# 08-USB_OTG.net
KiCad netlist of a schematic drawn in Altium Designer
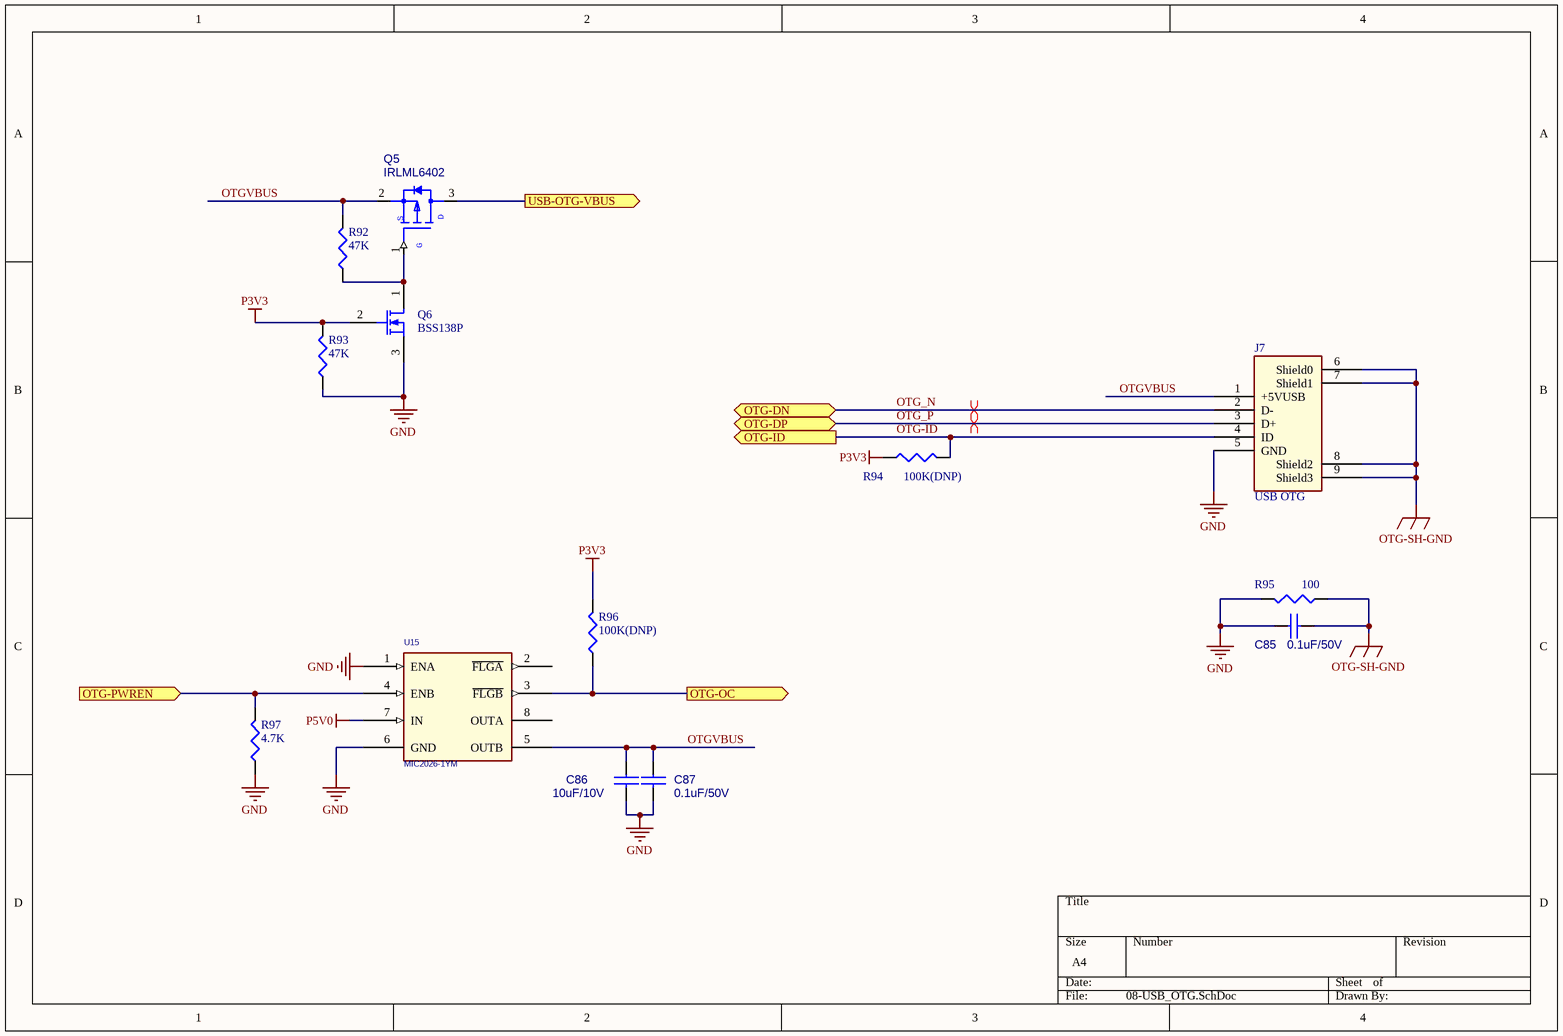
[diagram p0: 08-USB_OTG.SchDoc]

(export (version "E")
  (design (tool "Eeschema 10.0.6"))
  (components
    (comp (ref "C85") (value "0.1uF/50V") (libsource (lib "*") (part "CAP_Dup1")))
    (comp (ref "C86") (value "10uF/10V") (libsource (lib "*") (part "CAP_Dup1")))
    (comp (ref "C87") (value "0.1uF/50V") (libsource (lib "*") (part "CAP_Dup1")))
    (comp (ref "J7")
      (value "USB OTG")
      (footprint "MINIUSB-TYPEAB")
      (fields (field (name "PART NUMBER") "SP063100800"))
      (libsource (lib "*") (part "FOX_UH51543-JS7"))
    )
    (comp (ref "Q5")
      (value "IRLML6402")
      (footprint "MOSFET")
      (fields (field (name "PART NUMBER") "SB934010010"))
      (libsource (lib "*") (part "AO3401L_SOT23-3_0"))
    )
    (comp (ref "Q6")
      (value "BSS138P")
      (footprint "NPN")
      (description "N-Channel MOSFET")
      (fields (field (name "PUBLISHER") "Altium Limited"))
      (libsource (lib "Miscellaneous Devices") (part "MOSFET-N"))
    )
    (comp (ref "R92") (value "47K") (footprint "0402") (libsource (lib "*") (part "CR16-1003FM")))
    (comp (ref "R93") (value "47K") (footprint "0402") (libsource (lib "*") (part "CR16-1003FM")))
    (comp (ref "R94") (value "100K(DNP)") (footprint "0402") (libsource (lib "*") (part "CR16-1003FM")))
    (comp (ref "R95") (value "100") (footprint "0402") (libsource (lib "*") (part "CR16-1003FM")))
    (comp (ref "R96") (value "100K(DNP)") (footprint "0402") (libsource (lib "*") (part "CR16-1003FM")))
    (comp (ref "R97") (value "4.7K") (footprint "0402") (libsource (lib "*") (part "CR16-1003FM")))
    (comp (ref "U15")
      (value "MIC2026-1YM")
      (footprint "SO8")
      (description "IC LIN SW PWR ACTIVE HIGH DUAL 2.7V-5.5V 0.5A SOIC8")
      (libsource (lib "*") (part "MIC2526_8P"))
    )
  )
  (nets
    (net (code "1") (name "/OTG-ID") (class "Default")
      (node (ref "J7") (pin "4") (pinfunction "ID_4") (pintype "passive"))
      (node (ref "R94") (pin "2") (pinfunction "2_2") (pintype "passive"))
    )
    (net (code "2") (name "/OTG-OC") (class "Default")
      (node (ref "R96") (pin "1") (pinfunction "1_1") (pintype "passive"))
      (node (ref "U15") (pin "3") (pinfunction "~{FLGB}_3") (pintype "output"))
    )
    (net (code "3") (name "/OTG-PWREN") (class "Default")
      (node (ref "R97") (pin "2") (pinfunction "2_2") (pintype "passive"))
      (node (ref "U15") (pin "4") (pinfunction "ENB_4") (pintype "input"))
    )
    (net (code "4") (name "/OTGVBUS") (class "Default")
      (node (ref "C86") (pin "1") (pinfunction "1_1") (pintype "passive"))
      (node (ref "C87") (pin "1") (pinfunction "1_1") (pintype "passive"))
      (node (ref "J7") (pin "1") (pinfunction "+5VUSB_1") (pintype "passive"))
      (node (ref "Q5") (pin "2") (pinfunction "S_2") (pintype "passive"))
      (node (ref "R92") (pin "2") (pinfunction "2_2") (pintype "passive"))
      (node (ref "U15") (pin "5") (pinfunction "OUTB_5") (pintype "power_in"))
    )
    (net (code "5") (name "/OTG_N") (class "Default")
      (node (ref "J7") (pin "2") (pinfunction "D-_2") (pintype "passive"))
    )
    (net (code "6") (name "/OTG_P") (class "Default")
      (node (ref "J7") (pin "3") (pinfunction "D+_3") (pintype "passive"))
    )
    (net (code "7") (name "/USB-OTG-VBUS") (class "Default")
      (node (ref "Q5") (pin "3") (pinfunction "D_3") (pintype "passive"))
    )
    (net (code "8") (name "GND") (class "Default")
      (node (ref "C85") (pin "1") (pinfunction "1_1") (pintype "passive"))
      (node (ref "C86") (pin "2") (pinfunction "2_2") (pintype "passive"))
      (node (ref "C87") (pin "2") (pinfunction "2_2") (pintype "passive"))
      (node (ref "J7") (pin "5") (pinfunction "GND_5") (pintype "passive"))
      (node (ref "Q6") (pin "3") (pinfunction "S_3") (pintype "passive"))
      (node (ref "R93") (pin "1") (pinfunction "1_1") (pintype "passive"))
      (node (ref "R95") (pin "2") (pinfunction "2_2") (pintype "passive"))
      (node (ref "R97") (pin "1") (pinfunction "1_1") (pintype "passive"))
      (node (ref "U15") (pin "1") (pinfunction "ENA_1") (pintype "input"))
      (node (ref "U15") (pin "6") (pinfunction "GND_6") (pintype "power_in"))
    )
    (net (code "9") (name "Net-(Q5-G)") (class "Default")
      (node (ref "Q5") (pin "1") (pinfunction "G_1") (pintype "input"))
      (node (ref "Q6") (pin "1") (pinfunction "D_1") (pintype "passive"))
      (node (ref "R92") (pin "1") (pinfunction "1_1") (pintype "passive"))
    )
    (net (code "10") (name "OTG-SH-GND") (class "Default")
      (node (ref "C85") (pin "2") (pinfunction "2_2") (pintype "passive"))
      (node (ref "J7") (pin "6") (pinfunction "Shield0_6") (pintype "passive"))
      (node (ref "J7") (pin "7") (pinfunction "Shield1_7") (pintype "passive"))
      (node (ref "J7") (pin "8") (pinfunction "Shield2_8") (pintype "passive"))
      (node (ref "J7") (pin "9") (pinfunction "Shield3_9") (pintype "passive"))
      (node (ref "R95") (pin "1") (pinfunction "1_1") (pintype "passive"))
    )
    (net (code "11") (name "P3V3") (class "Default")
      (node (ref "Q6") (pin "2") (pinfunction "G_2") (pintype "passive"))
      (node (ref "R93") (pin "2") (pinfunction "2_2") (pintype "passive"))
      (node (ref "R94") (pin "1") (pinfunction "1_1") (pintype "passive"))
      (node (ref "R96") (pin "2") (pinfunction "2_2") (pintype "passive"))
    )
    (net (code "12") (name "P5V0") (class "Default")
      (node (ref "U15") (pin "7") (pinfunction "IN_7") (pintype "input"))
    )
    (net (code "13") (name "unconnected-(U15-OUTA-Pad8)") (class "Default")
      (node (ref "U15") (pin "8") (pinfunction "OUTA_8") (pintype "power_in"))
    )
    (net (code "14") (name "unconnected-(U15-~{FLGA}-Pad2)") (class "Default")
      (node (ref "U15") (pin "2") (pinfunction "~{FLGA}_2") (pintype "output"))
    )
  )
)
